# USB_UART.net
KiCad netlist of a schematic drawn in Altium Designer
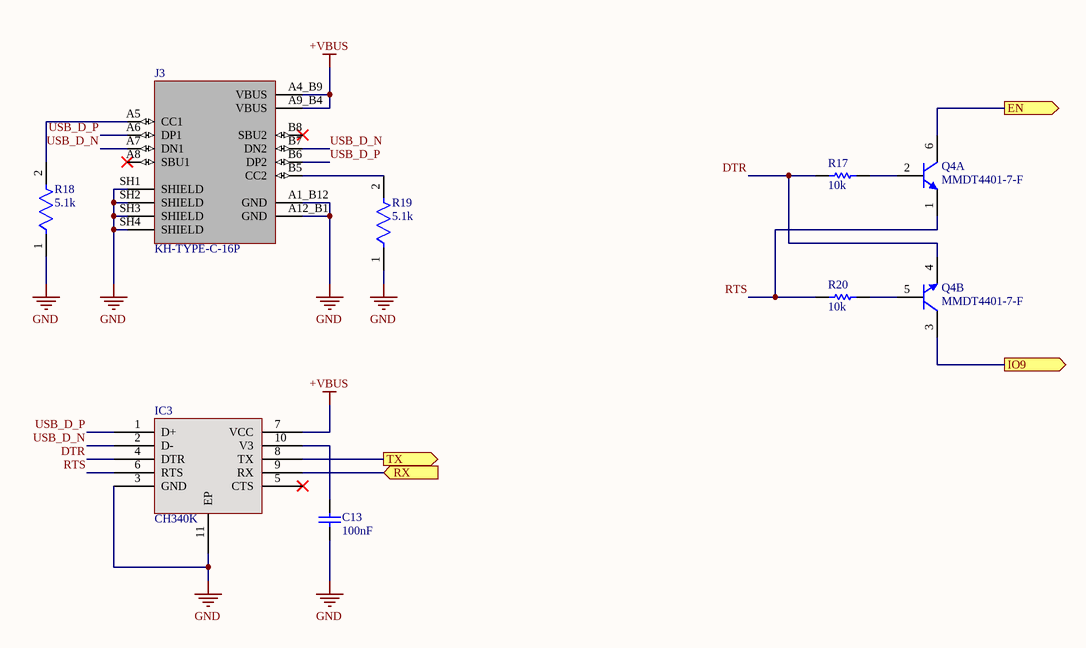
[diagram p0: USB_UART.SchDoc]

(export (version "E")
  (design (tool "Eeschema 10.0.6"))
  (components
    (comp (ref "C13")
      (value "GRM188R71H104KA93D")
      (footprint "CAPC1608X90X35ML10T15")
      (description "Chip Capacitor, 0.1 uF, +/- 10%, 50 V, -55 to 125 degC, 0603 (1608 Metric), RoHS, Tape and Reel")
      (fields
        (field (name "TOLERANCE") "10%")
        (field (name "CAPACITANCE") "100nF")
        (field (name "VOLTAGE") "50V")
      )
      (libsource (lib "Altium Content Vault") (part "CAP-NP-2"))
    )
    (comp (ref "IC3")
      (value "CH340K")
      (footprint "Leaded:ESOP-10L")
      (description "USB to Serial Port Chip CH340")
      (libsource (lib "USB_Controllers") (part "CH340K"))
    )
    (comp (ref "J3")
      (value "KH-TYPE-C-16P")
      (footprint "Leaded:KINGHELM_KH-TYPE-C-16P")
      (fields (field (name "MF") "kinghelm"))
      (libsource (lib "Connectors") (part "KH-TYPE-C-16P"))
    )
    (comp (ref "Q4")
      (value "MMDT4401-7-F")
      (footprint "NPN:Diodes SOT363-6P")
      (description "Small Signal Bipolar Transistor, 2-Element, NPN, Silicon")
      (fields (field (name "MANUFACTURER") "Diodes"))
      (libsource (lib "NPN") (part "Diodes MMDT4401-7-F"))
    )
    (comp (ref "R17")
      (value "10k")
      (footprint "RESC1609X50X30NL8T20")
      (description "Chip Resistor, 10 KOhm, +/- 1%, 100 mW, -55 to 155 degC, 0603 (1608 Metric), RoHS, Tape and Reel")
      (fields
        (field (name "MANUFACTURER") "Vishay Semiconductor")
        (field (name "Comment") "CRCW060310K0FKEA")
      )
      (libsource (lib "Altium Content Vault") (part "RES-2"))
    )
    (comp (ref "R18")
      (value "CRCW08055K10FKEA")
      (footprint "FP-CRCW0805-e3-MFG")
      (description "RES Thick Film, 5.1kΩ, 1%, 0.125W, 100ppm/°C, 0805")
      (fields (field (name "TOLERANCE") "1%") (field (name "RESISTANCE") "5.1k"))
      (libsource (lib "Altium Content Vault") (part "1029c3af85768c4190bb7ad29bc67b5"))
    )
    (comp (ref "R19")
      (value "CRCW08055K10FKEA")
      (footprint "FP-CRCW0805-e3-MFG")
      (description "RES Thick Film, 5.1kΩ, 1%, 0.125W, 100ppm/°C, 0805")
      (fields (field (name "TOLERANCE") "1%") (field (name "RESISTANCE") "5.1k"))
      (libsource (lib "Altium Content Vault") (part "1029c3af85768c4190bb7ad29bc67b5"))
    )
    (comp (ref "R20")
      (value "10k")
      (footprint "RESC1609X50X30NL8T20")
      (description "Chip Resistor, 10 KOhm, +/- 1%, 100 mW, -55 to 155 degC, 0603 (1608 Metric), RoHS, Tape and Reel")
      (fields
        (field (name "MANUFACTURER") "Vishay Semiconductor")
        (field (name "Comment") "CRCW060310K0FKEA")
      )
      (libsource (lib "Altium Content Vault") (part "RES-2"))
    )
  )
  (nets
    (net (code "1") (name "+VBUS") (class "Default")
      (node (ref "IC3") (pin "7") (pinfunction "VCC_7") (pintype "passive"))
      (node (ref "J3") (pin "A4_B9") (pinfunction "VBUS_A4_B9") (pintype "power_in"))
      (node (ref "J3") (pin "A9_B4") (pinfunction "VBUS_A9_B4") (pintype "power_in"))
    )
    (net (code "2") (name "/DTR") (class "Default")
      (node (ref "IC3") (pin "4") (pinfunction "DTR_4") (pintype "passive"))
      (node (ref "Q4") (pin "4") (pinfunction "E2_4") (pintype "passive"))
      (node (ref "R17") (pin "2") (pinfunction "2_2") (pintype "passive"))
    )
    (net (code "3") (name "/EN") (class "Default")
      (node (ref "Q4") (pin "6") (pinfunction "C1_6") (pintype "passive"))
    )
    (net (code "4") (name "/IO9") (class "Default")
      (node (ref "Q4") (pin "3") (pinfunction "C2_3") (pintype "passive"))
    )
    (net (code "5") (name "/RTS") (class "Default")
      (node (ref "IC3") (pin "6") (pinfunction "RTS_6") (pintype "passive"))
      (node (ref "Q4") (pin "1") (pinfunction "E1_1") (pintype "passive"))
      (node (ref "R20") (pin "2") (pinfunction "2_2") (pintype "passive"))
    )
    (net (code "6") (name "/RX") (class "Default")
      (node (ref "IC3") (pin "9") (pinfunction "RX_9") (pintype "passive"))
    )
    (net (code "7") (name "/TX") (class "Default")
      (node (ref "IC3") (pin "8") (pinfunction "TX_8") (pintype "passive"))
    )
    (net (code "8") (name "/USB_D_N") (class "Default")
      (node (ref "IC3") (pin "2") (pinfunction "D-_2") (pintype "passive"))
      (node (ref "J3") (pin "A7") (pinfunction "DN1_A7") (pintype "bidirectional"))
      (node (ref "J3") (pin "B7") (pinfunction "DN2_B7") (pintype "bidirectional"))
    )
    (net (code "9") (name "/USB_D_P") (class "Default")
      (node (ref "IC3") (pin "1") (pinfunction "D+_1") (pintype "passive"))
      (node (ref "J3") (pin "A6") (pinfunction "DP1_A6") (pintype "bidirectional"))
      (node (ref "J3") (pin "B6") (pinfunction "DP2_B6") (pintype "bidirectional"))
    )
    (net (code "10") (name "GND") (class "Default")
      (node (ref "C13") (pin "1") (pinfunction "1_1") (pintype "passive"))
      (node (ref "IC3") (pin "11") (pinfunction "EP_11") (pintype "passive"))
      (node (ref "IC3") (pin "3") (pinfunction "GND_3") (pintype "passive"))
      (node (ref "J3") (pin "A12_B1") (pinfunction "GND_A12_B1") (pintype "power_in"))
      (node (ref "J3") (pin "A1_B12") (pinfunction "GND_A1_B12") (pintype "power_in"))
      (node (ref "J3") (pin "SH1") (pinfunction "SHIELD_SH1") (pintype "passive"))
      (node (ref "J3") (pin "SH2") (pinfunction "SHIELD_SH2") (pintype "passive"))
      (node (ref "J3") (pin "SH3") (pinfunction "SHIELD_SH3") (pintype "passive"))
      (node (ref "J3") (pin "SH4") (pinfunction "SHIELD_SH4") (pintype "passive"))
      (node (ref "R18") (pin "1") (pinfunction "1_1") (pintype "passive"))
      (node (ref "R19") (pin "1") (pinfunction "1_1") (pintype "passive"))
    )
    (net (code "11") (name "Net-(IC3-V3)") (class "Default")
      (node (ref "C13") (pin "2") (pinfunction "2_2") (pintype "passive"))
      (node (ref "IC3") (pin "10") (pinfunction "V3_10") (pintype "passive"))
    )
    (net (code "12") (name "Net-(J3-CC1)") (class "Default")
      (node (ref "J3") (pin "A5") (pinfunction "CC1_A5") (pintype "bidirectional"))
      (node (ref "R18") (pin "2") (pinfunction "2_2") (pintype "passive"))
    )
    (net (code "13") (name "Net-(J3-CC2)") (class "Default")
      (node (ref "J3") (pin "B5") (pinfunction "CC2_B5") (pintype "bidirectional"))
      (node (ref "R19") (pin "2") (pinfunction "2_2") (pintype "passive"))
    )
    (net (code "14") (name "Net-(Q4A-B1)") (class "Default")
      (node (ref "Q4") (pin "2") (pinfunction "B1_2") (pintype "passive"))
      (node (ref "R17") (pin "1") (pinfunction "1_1") (pintype "passive"))
    )
    (net (code "15") (name "Net-(Q4B-B2)") (class "Default")
      (node (ref "Q4") (pin "5") (pinfunction "B2_5") (pintype "passive"))
      (node (ref "R20") (pin "1") (pinfunction "1_1") (pintype "passive"))
    )
    (net (code "16") (name "unconnected-(IC3-CTS-Pad5)") (class "Default")
      (node (ref "IC3") (pin "5") (pinfunction "CTS_5") (pintype "passive+no_connect"))
    )
    (net (code "17") (name "unconnected-(J3-SBU1-PadA8)") (class "Default")
      (node (ref "J3") (pin "A8") (pinfunction "SBU1_A8") (pintype "bidirectional+no_connect"))
    )
    (net (code "18") (name "unconnected-(J3-SBU2-PadB8)") (class "Default")
      (node (ref "J3") (pin "B8") (pinfunction "SBU2_B8") (pintype "bidirectional+no_connect"))
    )
  )
)
